# Schema_Plan_A.net
KiCad netlist of a schematic drawn in EasyEDA
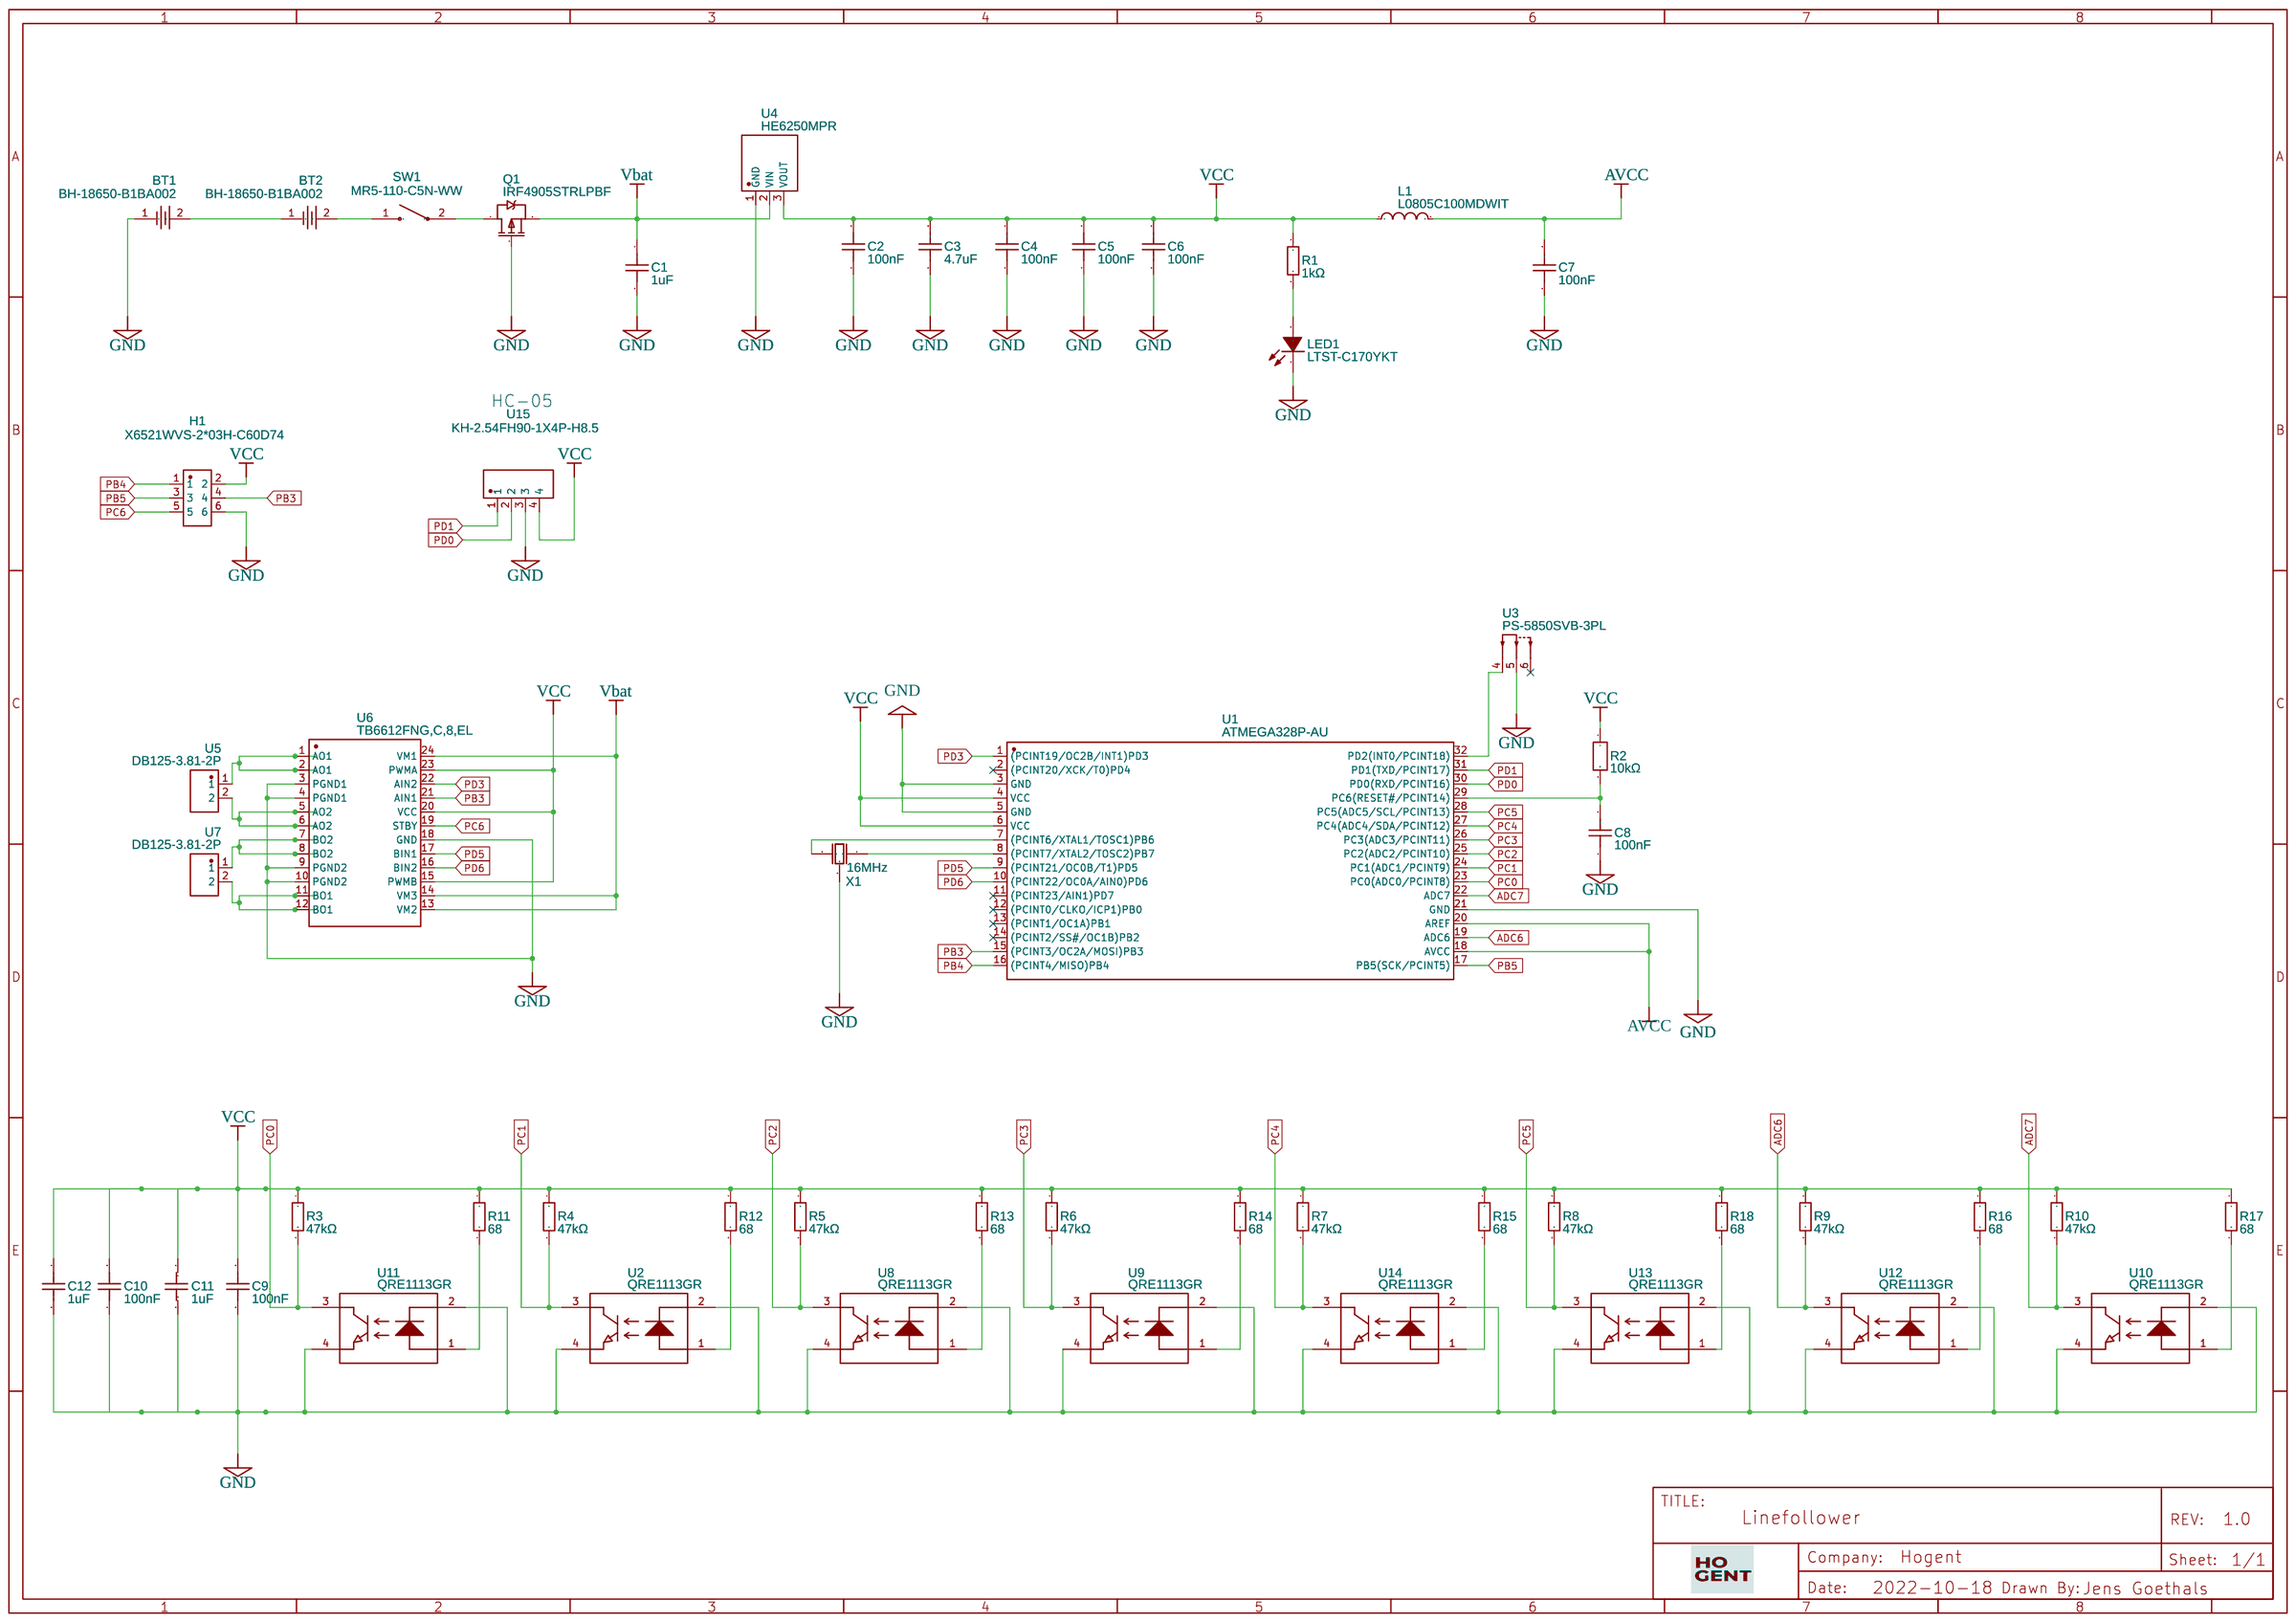
[diagram p0: schematic sheet]

(export (version "E")
  (design (tool "Eeschema 10.0.6"))
  (components
    (comp (ref "BT1")
      (value "BH-18650-B1BA002")
      (fields (field (name "BOM_Supplier Part") "C2988620"))
      (libsource (lib "") (part "BH-18650-B1BA002"))
    )
    (comp (ref "BT2")
      (value "BH-18650-B1BA002")
      (fields (field (name "BOM_Supplier Part") "C2988620"))
      (libsource (lib "") (part "BH-18650-B1BA002"))
    )
    (comp (ref "C1")
      (value "1uF")
      (fields
        (field (name "BOM_Manufacturer Part") "LMK212BJ105KD-T")
        (field (name "BOM_Supplier Part") "C92812")
      )
      (libsource (lib "") (part "LMK212BJ105KD-T_1"))
    )
    (comp (ref "C2")
      (value "100nF")
      (fields
        (field (name "BOM_Manufacturer Part") "LMK212SD104KG-T")
        (field (name "BOM_Supplier Part") "C386062")
      )
      (libsource (lib "") (part "LMK212SD104KG-T"))
    )
    (comp (ref "C3")
      (value "4.7uF")
      (fields
        (field (name "BOM_Manufacturer Part") "GCM21BC71A475KA73L")
        (field (name "BOM_Supplier Part") "C126583")
      )
      (libsource (lib "") (part "GCM21BC71A475KA73L"))
    )
    (comp (ref "C4")
      (value "100nF")
      (fields
        (field (name "BOM_Manufacturer Part") "LMK212SD104KG-T")
        (field (name "BOM_Supplier Part") "C386062")
      )
      (libsource (lib "") (part "LMK212SD104KG-T"))
    )
    (comp (ref "C5")
      (value "100nF")
      (fields
        (field (name "BOM_Manufacturer Part") "LMK212SD104KG-T")
        (field (name "BOM_Supplier Part") "C386062")
      )
      (libsource (lib "") (part "LMK212SD104KG-T"))
    )
    (comp (ref "C6")
      (value "100nF")
      (fields
        (field (name "BOM_Manufacturer Part") "LMK212SD104KG-T")
        (field (name "BOM_Supplier Part") "C386062")
      )
      (libsource (lib "") (part "LMK212SD104KG-T"))
    )
    (comp (ref "C7")
      (value "100nF")
      (fields
        (field (name "BOM_Manufacturer Part") "LMK212SD104KG-T")
        (field (name "BOM_Supplier Part") "C386062")
      )
      (libsource (lib "") (part "LMK212SD104KG-T"))
    )
    (comp (ref "C8")
      (value "100nF")
      (fields
        (field (name "BOM_Manufacturer Part") "LMK212SD104KG-T")
        (field (name "BOM_Supplier Part") "C386062")
      )
      (libsource (lib "") (part "LMK212SD104KG-T"))
    )
    (comp (ref "C9")
      (value "100nF")
      (fields
        (field (name "BOM_Manufacturer Part") "LMK212SD104KG-T")
        (field (name "BOM_Supplier Part") "C386062")
      )
      (libsource (lib "") (part "LMK212SD104KG-T"))
    )
    (comp (ref "C10")
      (value "100nF")
      (fields
        (field (name "BOM_Manufacturer Part") "LMK212SD104KG-T")
        (field (name "BOM_Supplier Part") "C386062")
      )
      (libsource (lib "") (part "LMK212SD104KG-T"))
    )
    (comp (ref "C11")
      (value "1uF")
      (fields
        (field (name "BOM_Manufacturer Part") "LMK212BJ105KD-T")
        (field (name "BOM_Supplier Part") "C92812")
      )
      (libsource (lib "") (part "LMK212BJ105KD-T"))
    )
    (comp (ref "C12")
      (value "1uF")
      (fields
        (field (name "BOM_Manufacturer Part") "LMK212BJ105KD-T")
        (field (name "BOM_Supplier Part") "C92812")
      )
      (libsource (lib "") (part "LMK212BJ105KD-T_1"))
    )
    (comp (ref "H1")
      (value "X6521WVS-2*03H-C60D74")
      (fields (field (name "BOM_Supplier Part") "C780054"))
      (libsource (lib "") (part "X6521WVS-2*03H-C60D74"))
    )
    (comp (ref "L1")
      (value "L0805C100MDWIT")
      (fields (field (name "BOM_Supplier Part") "C696787"))
      (libsource (lib "") (part "L0805C100MDWIT"))
    )
    (comp (ref "LED1")
      (value "LTST-C170YKT")
      (fields (field (name "BOM_Supplier Part") "C125092"))
      (libsource (lib "") (part "LTST-C170YKT"))
    )
    (comp (ref "Q1")
      (value "IRF4905STRLPBF")
      (fields (field (name "BOM_Supplier Part") "C2620"))
      (libsource (lib "") (part "IRF4905STRLPBF"))
    )
    (comp (ref "R1")
      (value "1kΩ")
      (fields
        (field (name "BOM_Manufacturer Part") "ARG05BTC1001")
        (field (name "BOM_Supplier Part") "C309081")
      )
      (libsource (lib "") (part "ARG05BTC1001"))
    )
    (comp (ref "R2")
      (value "10kΩ")
      (fields
        (field (name "BOM_Manufacturer Part") "ARG05BTC1002")
        (field (name "BOM_Supplier Part") "C406725")
      )
      (libsource (lib "") (part "ARG05BTC1002"))
    )
    (comp (ref "R3")
      (value "47kΩ")
      (fields
        (field (name "BOM_Manufacturer Part") "AECR0805F47K0K9")
        (field (name "BOM_Supplier Part") "C328397")
      )
      (libsource (lib "") (part "AECR0805F47K0K9"))
    )
    (comp (ref "R4")
      (value "47kΩ")
      (fields
        (field (name "BOM_Manufacturer Part") "AECR0805F47K0K9")
        (field (name "BOM_Supplier Part") "C328397")
      )
      (libsource (lib "") (part "AECR0805F47K0K9"))
    )
    (comp (ref "R5")
      (value "47kΩ")
      (fields
        (field (name "BOM_Manufacturer Part") "AECR0805F47K0K9")
        (field (name "BOM_Supplier Part") "C328397")
      )
      (libsource (lib "") (part "AECR0805F47K0K9"))
    )
    (comp (ref "R6")
      (value "47kΩ")
      (fields
        (field (name "BOM_Manufacturer Part") "AECR0805F47K0K9")
        (field (name "BOM_Supplier Part") "C328397")
      )
      (libsource (lib "") (part "AECR0805F47K0K9"))
    )
    (comp (ref "R7")
      (value "47kΩ")
      (fields
        (field (name "BOM_Manufacturer Part") "AECR0805F47K0K9")
        (field (name "BOM_Supplier Part") "C328397")
      )
      (libsource (lib "") (part "AECR0805F47K0K9"))
    )
    (comp (ref "R8")
      (value "47kΩ")
      (fields
        (field (name "BOM_Manufacturer Part") "AECR0805F47K0K9")
        (field (name "BOM_Supplier Part") "C328397")
      )
      (libsource (lib "") (part "AECR0805F47K0K9"))
    )
    (comp (ref "R9")
      (value "47kΩ")
      (fields
        (field (name "BOM_Manufacturer Part") "AECR0805F47K0K9")
        (field (name "BOM_Supplier Part") "C328397")
      )
      (libsource (lib "") (part "AECR0805F47K0K9"))
    )
    (comp (ref "R10")
      (value "47kΩ")
      (fields
        (field (name "BOM_Manufacturer Part") "AECR0805F47K0K9")
        (field (name "BOM_Supplier Part") "C328397")
      )
      (libsource (lib "") (part "AECR0805F47K0K9"))
    )
    (comp (ref "R11")
      (value "68")
      (fields
        (field (name "BOM_Manufacturer Part") "RC0805FR-0768RL")
        (field (name "BOM_Supplier Part") "C137498")
      )
      (libsource (lib "") (part "RC0805FR-0768RL"))
    )
    (comp (ref "R12")
      (value "68")
      (fields
        (field (name "BOM_Manufacturer Part") "RC0805FR-0768RL")
        (field (name "BOM_Supplier Part") "C137498")
      )
      (libsource (lib "") (part "RC0805FR-0768RL"))
    )
    (comp (ref "R13")
      (value "68")
      (fields
        (field (name "BOM_Manufacturer Part") "RC0805FR-0768RL")
        (field (name "BOM_Supplier Part") "C137498")
      )
      (libsource (lib "") (part "RC0805FR-0768RL"))
    )
    (comp (ref "R14")
      (value "68")
      (fields
        (field (name "BOM_Manufacturer Part") "RC0805FR-0768RL")
        (field (name "BOM_Supplier Part") "C137498")
      )
      (libsource (lib "") (part "RC0805FR-0768RL"))
    )
    (comp (ref "R15")
      (value "68")
      (fields
        (field (name "BOM_Manufacturer Part") "RC0805FR-0768RL")
        (field (name "BOM_Supplier Part") "C137498")
      )
      (libsource (lib "") (part "RC0805FR-0768RL"))
    )
    (comp (ref "R16")
      (value "68")
      (fields
        (field (name "BOM_Manufacturer Part") "RC0805FR-0768RL")
        (field (name "BOM_Supplier Part") "C137498")
      )
      (libsource (lib "") (part "RC0805FR-0768RL"))
    )
    (comp (ref "R17")
      (value "68")
      (fields
        (field (name "BOM_Manufacturer Part") "RC0805FR-0768RL")
        (field (name "BOM_Supplier Part") "C137498")
      )
      (libsource (lib "") (part "RC0805FR-0768RL"))
    )
    (comp (ref "R18")
      (value "68")
      (fields
        (field (name "BOM_Manufacturer Part") "RC0805FR-0768RL")
        (field (name "BOM_Supplier Part") "C137498")
      )
      (libsource (lib "") (part "RC0805FR-0768RL"))
    )
    (comp (ref "SW1")
      (value "MR5-110-C5N-WW")
      (fields (field (name "BOM_Supplier Part") "C2829507"))
      (libsource (lib "") (part "MR5-110-C5N-WW"))
    )
    (comp (ref "U1")
      (value "ATMEGA328P-AU")
      (fields (field (name "BOM_Supplier Part") "C14877"))
      (libsource (lib "") (part "ATMEGA328P-AU"))
    )
    (comp (ref "U2")
      (value "QRE1113GR")
      (fields (field (name "BOM_Supplier Part") "C232862"))
      (libsource (lib "") (part "QRE1113GR_3"))
    )
    (comp (ref "U3")
      (value "PS-5850SVB-3PL")
      (fields (field (name "BOM_Supplier Part") "C5159077"))
      (libsource (lib "") (part "PS-5850SVB-3PL"))
    )
    (comp (ref "U4")
      (value "HE6250MPR")
      (fields (field (name "BOM_Supplier Part") "C711940"))
      (libsource (lib "") (part "HE6250MPR"))
    )
    (comp (ref "U5")
      (value "DB125-3.81-2P")
      (fields (field (name "BOM_Supplier Part") "C395878"))
      (libsource (lib "") (part "DB125-3.81-2P"))
    )
    (comp (ref "U6")
      (value "TB6612FNG,C,8,EL")
      (fields (field (name "BOM_Supplier Part") "C141517"))
      (libsource (lib "") (part "Unknown_500_-570"))
    )
    (comp (ref "U7")
      (value "DB125-3.81-2P")
      (fields (field (name "BOM_Supplier Part") "C395878"))
      (libsource (lib "") (part "DB125-3.81-2P"))
    )
    (comp (ref "U8")
      (value "QRE1113GR")
      (fields (field (name "BOM_Supplier Part") "C232862"))
      (libsource (lib "") (part "QRE1113GR"))
    )
    (comp (ref "U9")
      (value "QRE1113GR")
      (fields (field (name "BOM_Supplier Part") "C232862"))
      (libsource (lib "") (part "QRE1113GR_4"))
    )
    (comp (ref "U10")
      (value "QRE1113GR")
      (fields (field (name "BOM_Supplier Part") "C232862"))
      (libsource (lib "") (part "QRE1113GR_2"))
    )
    (comp (ref "U11")
      (value "QRE1113GR")
      (fields (field (name "BOM_Supplier Part") "C232862"))
      (libsource (lib "") (part "QRE1113GR_2"))
    )
    (comp (ref "U12")
      (value "QRE1113GR")
      (fields (field (name "BOM_Supplier Part") "C232862"))
      (libsource (lib "") (part "QRE1113GR_6"))
    )
    (comp (ref "U13")
      (value "QRE1113GR")
      (fields (field (name "BOM_Supplier Part") "C232862"))
      (libsource (lib "") (part "QRE1113GR_1"))
    )
    (comp (ref "U14")
      (value "QRE1113GR")
      (fields (field (name "BOM_Supplier Part") "C232862"))
      (libsource (lib "") (part "QRE1113GR_5"))
    )
    (comp (ref "U15")
      (value "KH-2.54FH90-1X4P-H8.5")
      (fields (field (name "BOM_Supplier Part") "C2932680"))
      (libsource (lib "") (part "KH-2.54FH90-1X4P-H8.5"))
    )
    (comp (ref "X1")
      (value "16MHz")
      (fields
        (field (name "BOM_Manufacturer Part") "CSTNE16M0V53C000R0")
        (field (name "BOM_Supplier Part") "C882606")
      )
      (libsource (lib "") (part "CSTNE16M0V53C000R0"))
    )
  )
  (nets
    (net (code "1") (name "ADC6") (class "Default")
      (node (ref "R9") (pin "2") (pinfunction "2_2") (pintype "unspecified"))
      (node (ref "U1") (pin "19") (pinfunction "ADC6_19") (pintype "unspecified"))
      (node (ref "U12") (pin "3") (pinfunction "3_3") (pintype "input"))
    )
    (net (code "2") (name "ADC7") (class "Default")
      (node (ref "R10") (pin "2") (pinfunction "2_2") (pintype "unspecified"))
      (node (ref "U1") (pin "22") (pinfunction "ADC7_22") (pintype "unspecified"))
      (node (ref "U10") (pin "3") (pinfunction "3_3") (pintype "input"))
    )
    (net (code "3") (name "AVCC") (class "Default")
      (node (ref "C7") (pin "2") (pinfunction "2_2") (pintype "unspecified"))
      (node (ref "L1") (pin "2") (pinfunction "2_2") (pintype "unspecified"))
      (node (ref "U1") (pin "18") (pinfunction "AVCC_18") (pintype "unspecified"))
      (node (ref "U1") (pin "20") (pinfunction "AREF_20") (pintype "unspecified"))
    )
    (net (code "4") (name "GND") (class "Default")
      (node (ref "BT1") (pin "1") (pinfunction "1_1") (pintype "input"))
      (node (ref "C1") (pin "2") (pinfunction "2_2") (pintype "unspecified"))
      (node (ref "C10") (pin "1") (pinfunction "1_1") (pintype "unspecified"))
      (node (ref "C11") (pin "2") (pinfunction "2_2") (pintype "unspecified"))
      (node (ref "C12") (pin "2") (pinfunction "2_2") (pintype "unspecified"))
      (node (ref "C2") (pin "1") (pinfunction "1_1") (pintype "unspecified"))
      (node (ref "C3") (pin "1") (pinfunction "1_1") (pintype "unspecified"))
      (node (ref "C4") (pin "1") (pinfunction "1_1") (pintype "unspecified"))
      (node (ref "C5") (pin "1") (pinfunction "1_1") (pintype "unspecified"))
      (node (ref "C6") (pin "1") (pinfunction "1_1") (pintype "unspecified"))
      (node (ref "C7") (pin "1") (pinfunction "1_1") (pintype "unspecified"))
      (node (ref "C8") (pin "1") (pinfunction "1_1") (pintype "unspecified"))
      (node (ref "C9") (pin "1") (pinfunction "1_1") (pintype "unspecified"))
      (node (ref "H1") (pin "6") (pinfunction "6_6") (pintype "unspecified"))
      (node (ref "LED1") (pin "1") (pinfunction "1_1") (pintype "unspecified"))
      (node (ref "Q1") (pin "1") (pinfunction "G_1") (pintype "unspecified"))
      (node (ref "U1") (pin "21") (pinfunction "GND_21") (pintype "unspecified"))
      (node (ref "U1") (pin "3") (pinfunction "GND_3") (pintype "unspecified"))
      (node (ref "U1") (pin "5") (pinfunction "GND_5") (pintype "unspecified"))
      (node (ref "U10") (pin "2") (pinfunction "2_2") (pintype "input"))
      (node (ref "U10") (pin "4") (pinfunction "4_4") (pintype "input"))
      (node (ref "U11") (pin "2") (pinfunction "2_2") (pintype "input"))
      (node (ref "U11") (pin "4") (pinfunction "4_4") (pintype "input"))
      (node (ref "U12") (pin "2") (pinfunction "2_2") (pintype "input"))
      (node (ref "U12") (pin "4") (pinfunction "4_4") (pintype "input"))
      (node (ref "U13") (pin "2") (pinfunction "2_2") (pintype "input"))
      (node (ref "U13") (pin "4") (pinfunction "4_4") (pintype "input"))
      (node (ref "U14") (pin "2") (pinfunction "2_2") (pintype "input"))
      (node (ref "U14") (pin "4") (pinfunction "4_4") (pintype "input"))
      (node (ref "U15") (pin "3") (pinfunction "3_3") (pintype "unspecified"))
      (node (ref "U2") (pin "2") (pinfunction "2_2") (pintype "input"))
      (node (ref "U2") (pin "4") (pinfunction "4_4") (pintype "input"))
      (node (ref "U3") (pin "5") (pinfunction "5_5") (pintype "unspecified"))
      (node (ref "U4") (pin "1") (pinfunction "GND_1") (pintype "unspecified"))
      (node (ref "U6") (pin "10") (pinfunction "PGND2_10") (pintype "unspecified"))
      (node (ref "U6") (pin "18") (pinfunction "GND_18") (pintype "unspecified"))
      (node (ref "U6") (pin "3") (pinfunction "PGND1_3") (pintype "unspecified"))
      (node (ref "U6") (pin "4") (pinfunction "PGND1_4") (pintype "unspecified"))
      (node (ref "U6") (pin "9") (pinfunction "PGND2_9") (pintype "unspecified"))
      (node (ref "U8") (pin "2") (pinfunction "2_2") (pintype "input"))
      (node (ref "U8") (pin "4") (pinfunction "4_4") (pintype "input"))
      (node (ref "U9") (pin "2") (pinfunction "2_2") (pintype "input"))
      (node (ref "U9") (pin "4") (pinfunction "4_4") (pintype "input"))
      (node (ref "X1") (pin "2") (pinfunction "GND_2") (pintype "input"))
    )
    (net (code "5") (name "Net-(BT1-Pad2)") (class "Default")
      (node (ref "BT1") (pin "2") (pinfunction "2_2") (pintype "input"))
      (node (ref "BT2") (pin "1") (pinfunction "1_1") (pintype "input"))
    )
    (net (code "6") (name "Net-(BT2-Pad2)") (class "Default")
      (node (ref "BT2") (pin "2") (pinfunction "2_2") (pintype "input"))
      (node (ref "SW1") (pin "1") (pinfunction "1_1") (pintype "unspecified"))
    )
    (net (code "7") (name "Net-(LED1-Pad2)") (class "Default")
      (node (ref "LED1") (pin "2") (pinfunction "2_2") (pintype "unspecified"))
      (node (ref "R1") (pin "2") (pinfunction "2_2") (pintype "unspecified"))
    )
    (net (code "8") (name "Net-(Q1-D)") (class "Default")
      (node (ref "Q1") (pin "4") (pinfunction "D_4") (pintype "unspecified"))
      (node (ref "SW1") (pin "2") (pinfunction "2_2") (pintype "unspecified"))
    )
    (net (code "9") (name "Net-(R11-Pad2)") (class "Default")
      (node (ref "R11") (pin "2") (pinfunction "2_2") (pintype "input"))
      (node (ref "U11") (pin "1") (pinfunction "1_1") (pintype "input"))
    )
    (net (code "10") (name "Net-(R12-Pad2)") (class "Default")
      (node (ref "R12") (pin "2") (pinfunction "2_2") (pintype "input"))
      (node (ref "U2") (pin "1") (pinfunction "1_1") (pintype "input"))
    )
    (net (code "11") (name "Net-(R13-Pad2)") (class "Default")
      (node (ref "R13") (pin "2") (pinfunction "2_2") (pintype "input"))
      (node (ref "U8") (pin "1") (pinfunction "1_1") (pintype "input"))
    )
    (net (code "12") (name "Net-(R14-Pad2)") (class "Default")
      (node (ref "R14") (pin "2") (pinfunction "2_2") (pintype "input"))
      (node (ref "U9") (pin "1") (pinfunction "1_1") (pintype "input"))
    )
    (net (code "13") (name "Net-(R15-Pad2)") (class "Default")
      (node (ref "R15") (pin "2") (pinfunction "2_2") (pintype "input"))
      (node (ref "U14") (pin "1") (pinfunction "1_1") (pintype "input"))
    )
    (net (code "14") (name "Net-(R16-Pad2)") (class "Default")
      (node (ref "R16") (pin "2") (pinfunction "2_2") (pintype "input"))
      (node (ref "U12") (pin "1") (pinfunction "1_1") (pintype "input"))
    )
    (net (code "15") (name "Net-(R17-Pad2)") (class "Default")
      (node (ref "R17") (pin "2") (pinfunction "2_2") (pintype "input"))
      (node (ref "U10") (pin "1") (pinfunction "1_1") (pintype "input"))
    )
    (net (code "16") (name "Net-(R18-Pad2)") (class "Default")
      (node (ref "R18") (pin "2") (pinfunction "2_2") (pintype "input"))
      (node (ref "U13") (pin "1") (pinfunction "1_1") (pintype "input"))
    )
    (net (code "17") (name "Net-(U1-(PCINT6{slash}XTAL1{slash}TOSC1)PB6)") (class "Default")
      (node (ref "U1") (pin "7") (pinfunction "(PCINT6/XTAL1/TOSC1)PB6_7") (pintype "unspecified"))
      (node (ref "X1") (pin "3") (pinfunction "OSC2_3") (pintype "input"))
    )
    (net (code "18") (name "Net-(U1-(PCINT7{slash}XTAL2{slash}TOSC2)PB7)") (class "Default")
      (node (ref "U1") (pin "8") (pinfunction "(PCINT7/XTAL2/TOSC2)PB7_8") (pintype "unspecified"))
      (node (ref "X1") (pin "1") (pinfunction "OSC1_1") (pintype "input"))
    )
    (net (code "19") (name "Net-(U1-PC6(RESET#{slash}PCINT14))") (class "Default")
      (node (ref "C8") (pin "2") (pinfunction "2_2") (pintype "unspecified"))
      (node (ref "R2") (pin "2") (pinfunction "2_2") (pintype "unspecified"))
      (node (ref "U1") (pin "29") (pinfunction "PC6(RESET#/PCINT14)_29") (pintype "unspecified"))
    )
    (net (code "20") (name "Net-(U1-PD2(INT0{slash}PCINT18))") (class "Default")
      (node (ref "U1") (pin "32") (pinfunction "PD2(INT0/PCINT18)_32") (pintype "unspecified"))
      (node (ref "U3") (pin "4") (pinfunction "4_4") (pintype "unspecified"))
    )
    (net (code "21") (name "Net-(U5-Pad1)") (class "Default")
      (node (ref "U5") (pin "1") (pinfunction "1_1") (pintype "unspecified"))
      (node (ref "U6") (pin "1") (pinfunction "AO1_1") (pintype "unspecified"))
      (node (ref "U6") (pin "2") (pinfunction "AO1_2") (pintype "unspecified"))
    )
    (net (code "22") (name "Net-(U5-Pad2)") (class "Default")
      (node (ref "U5") (pin "2") (pinfunction "2_2") (pintype "unspecified"))
      (node (ref "U6") (pin "5") (pinfunction "AO2_5") (pintype "unspecified"))
      (node (ref "U6") (pin "6") (pinfunction "AO2_6") (pintype "unspecified"))
    )
    (net (code "23") (name "Net-(U6-BO1-Pad11)") (class "Default")
      (node (ref "U6") (pin "11") (pinfunction "BO1_11") (pintype "unspecified"))
      (node (ref "U6") (pin "12") (pinfunction "BO1_12") (pintype "unspecified"))
      (node (ref "U7") (pin "2") (pinfunction "2_2") (pintype "unspecified"))
    )
    (net (code "24") (name "Net-(U6-BO2-Pad7)") (class "Default")
      (node (ref "U6") (pin "7") (pinfunction "BO2_7") (pintype "unspecified"))
      (node (ref "U6") (pin "8") (pinfunction "BO2_8") (pintype "unspecified"))
      (node (ref "U7") (pin "1") (pinfunction "1_1") (pintype "unspecified"))
    )
    (net (code "25") (name "PB3") (class "Default")
      (node (ref "H1") (pin "4") (pinfunction "4_4") (pintype "unspecified"))
      (node (ref "U1") (pin "15") (pinfunction "(PCINT3/OC2A/MOSI)PB3_15") (pintype "unspecified"))
      (node (ref "U6") (pin "21") (pinfunction "AIN1_21") (pintype "unspecified"))
    )
    (net (code "26") (name "PB4") (class "Default")
      (node (ref "H1") (pin "1") (pinfunction "1_1") (pintype "unspecified"))
      (node (ref "U1") (pin "16") (pinfunction "(PCINT4/MISO)PB4_16") (pintype "unspecified"))
    )
    (net (code "27") (name "PB5") (class "Default")
      (node (ref "H1") (pin "3") (pinfunction "3_3") (pintype "unspecified"))
      (node (ref "U1") (pin "17") (pinfunction "PB5(SCK/PCINT5)_17") (pintype "unspecified"))
    )
    (net (code "28") (name "PC0") (class "Default")
      (node (ref "R3") (pin "2") (pinfunction "2_2") (pintype "unspecified"))
      (node (ref "U1") (pin "23") (pinfunction "PC0(ADC0/PCINT8)_23") (pintype "unspecified"))
      (node (ref "U11") (pin "3") (pinfunction "3_3") (pintype "input"))
    )
    (net (code "29") (name "PC1") (class "Default")
      (node (ref "R4") (pin "2") (pinfunction "2_2") (pintype "unspecified"))
      (node (ref "U1") (pin "24") (pinfunction "PC1(ADC1/PCINT9)_24") (pintype "unspecified"))
      (node (ref "U2") (pin "3") (pinfunction "3_3") (pintype "input"))
    )
    (net (code "30") (name "PC2") (class "Default")
      (node (ref "R5") (pin "2") (pinfunction "2_2") (pintype "unspecified"))
      (node (ref "U1") (pin "25") (pinfunction "PC2(ADC2/PCINT10)_25") (pintype "unspecified"))
      (node (ref "U8") (pin "3") (pinfunction "3_3") (pintype "input"))
    )
    (net (code "31") (name "PC3") (class "Default")
      (node (ref "R6") (pin "2") (pinfunction "2_2") (pintype "unspecified"))
      (node (ref "U1") (pin "26") (pinfunction "PC3(ADC3/PCINT11)_26") (pintype "unspecified"))
      (node (ref "U9") (pin "3") (pinfunction "3_3") (pintype "input"))
    )
    (net (code "32") (name "PC4") (class "Default")
      (node (ref "R7") (pin "2") (pinfunction "2_2") (pintype "unspecified"))
      (node (ref "U1") (pin "27") (pinfunction "PC4(ADC4/SDA/PCINT12)_27") (pintype "unspecified"))
      (node (ref "U14") (pin "3") (pinfunction "3_3") (pintype "input"))
    )
    (net (code "33") (name "PC5") (class "Default")
      (node (ref "R8") (pin "2") (pinfunction "2_2") (pintype "unspecified"))
      (node (ref "U1") (pin "28") (pinfunction "PC5(ADC5/SCL/PCINT13)_28") (pintype "unspecified"))
      (node (ref "U13") (pin "3") (pinfunction "3_3") (pintype "input"))
    )
    (net (code "34") (name "PC6") (class "Default")
      (node (ref "H1") (pin "5") (pinfunction "5_5") (pintype "unspecified"))
      (node (ref "U6") (pin "19") (pinfunction "STBY_19") (pintype "unspecified"))
    )
    (net (code "35") (name "PD0") (class "Default")
      (node (ref "U1") (pin "30") (pinfunction "PD0(RXD/PCINT16)_30") (pintype "unspecified"))
      (node (ref "U15") (pin "2") (pinfunction "2_2") (pintype "unspecified"))
    )
    (net (code "36") (name "PD1") (class "Default")
      (node (ref "U1") (pin "31") (pinfunction "PD1(TXD/PCINT17)_31") (pintype "unspecified"))
      (node (ref "U15") (pin "1") (pinfunction "1_1") (pintype "unspecified"))
    )
    (net (code "37") (name "PD3") (class "Default")
      (node (ref "U1") (pin "1") (pinfunction "(PCINT19/OC2B/INT1)PD3_1") (pintype "unspecified"))
      (node (ref "U6") (pin "22") (pinfunction "AIN2_22") (pintype "unspecified"))
    )
    (net (code "38") (name "PD5") (class "Default")
      (node (ref "U1") (pin "9") (pinfunction "(PCINT21/OC0B/T1)PD5_9") (pintype "unspecified"))
      (node (ref "U6") (pin "17") (pinfunction "BIN1_17") (pintype "unspecified"))
    )
    (net (code "39") (name "PD6") (class "Default")
      (node (ref "U1") (pin "10") (pinfunction "(PCINT22/OC0A/AIN0)PD6_10") (pintype "unspecified"))
      (node (ref "U6") (pin "16") (pinfunction "BIN2_16") (pintype "unspecified"))
    )
    (net (code "40") (name "VCC") (class "Default")
      (node (ref "C10") (pin "2") (pinfunction "2_2") (pintype "unspecified"))
      (node (ref "C11") (pin "1") (pinfunction "1_1") (pintype "unspecified"))
      (node (ref "C12") (pin "1") (pinfunction "1_1") (pintype "unspecified"))
      (node (ref "C2") (pin "2") (pinfunction "2_2") (pintype "unspecified"))
      (node (ref "C3") (pin "2") (pinfunction "2_2") (pintype "unspecified"))
      (node (ref "C4") (pin "2") (pinfunction "2_2") (pintype "unspecified"))
      (node (ref "C5") (pin "2") (pinfunction "2_2") (pintype "unspecified"))
      (node (ref "C6") (pin "2") (pinfunction "2_2") (pintype "unspecified"))
      (node (ref "C9") (pin "2") (pinfunction "2_2") (pintype "unspecified"))
      (node (ref "H1") (pin "2") (pinfunction "2_2") (pintype "unspecified"))
      (node (ref "L1") (pin "1") (pinfunction "1_1") (pintype "unspecified"))
      (node (ref "R1") (pin "1") (pinfunction "1_1") (pintype "unspecified"))
      (node (ref "R10") (pin "1") (pinfunction "1_1") (pintype "unspecified"))
      (node (ref "R11") (pin "1") (pinfunction "1_1") (pintype "input"))
      (node (ref "R12") (pin "1") (pinfunction "1_1") (pintype "input"))
      (node (ref "R13") (pin "1") (pinfunction "1_1") (pintype "input"))
      (node (ref "R14") (pin "1") (pinfunction "1_1") (pintype "input"))
      (node (ref "R15") (pin "1") (pinfunction "1_1") (pintype "input"))
      (node (ref "R16") (pin "1") (pinfunction "1_1") (pintype "input"))
      (node (ref "R17") (pin "1") (pinfunction "1_1") (pintype "input"))
      (node (ref "R18") (pin "1") (pinfunction "1_1") (pintype "input"))
      (node (ref "R2") (pin "1") (pinfunction "1_1") (pintype "unspecified"))
      (node (ref "R3") (pin "1") (pinfunction "1_1") (pintype "unspecified"))
      (node (ref "R4") (pin "1") (pinfunction "1_1") (pintype "unspecified"))
      (node (ref "R5") (pin "1") (pinfunction "1_1") (pintype "unspecified"))
      (node (ref "R6") (pin "1") (pinfunction "1_1") (pintype "unspecified"))
      (node (ref "R7") (pin "1") (pinfunction "1_1") (pintype "unspecified"))
      (node (ref "R8") (pin "1") (pinfunction "1_1") (pintype "unspecified"))
      (node (ref "R9") (pin "1") (pinfunction "1_1") (pintype "unspecified"))
      (node (ref "U1") (pin "4") (pinfunction "VCC_4") (pintype "unspecified"))
      (node (ref "U1") (pin "6") (pinfunction "VCC_6") (pintype "unspecified"))
      (node (ref "U15") (pin "4") (pinfunction "4_4") (pintype "unspecified"))
      (node (ref "U4") (pin "3") (pinfunction "VOUT_3") (pintype "unspecified"))
      (node (ref "U6") (pin "15") (pinfunction "PWMB_15") (pintype "unspecified"))
      (node (ref "U6") (pin "20") (pinfunction "VCC_20") (pintype "unspecified"))
      (node (ref "U6") (pin "23") (pinfunction "PWMA_23") (pintype "unspecified"))
    )
    (net (code "41") (name "Vbat") (class "Default")
      (node (ref "C1") (pin "1") (pinfunction "1_1") (pintype "unspecified"))
      (node (ref "Q1") (pin "3") (pinfunction "S_3") (pintype "unspecified"))
      (node (ref "U4") (pin "2") (pinfunction "VIN_2") (pintype "unspecified"))
      (node (ref "U6") (pin "13") (pinfunction "VM2_13") (pintype "unspecified"))
      (node (ref "U6") (pin "14") (pinfunction "VM3_14") (pintype "unspecified"))
      (node (ref "U6") (pin "24") (pinfunction "VM1_24") (pintype "unspecified"))
    )
    (net (code "42") (name "unconnected-(U1-(PCINT0{slash}CLKO{slash}ICP1)PB0-Pad12)") (class "Default")
      (node (ref "U1") (pin "12") (pinfunction "(PCINT0/CLKO/ICP1)PB0_12") (pintype "unspecified+no_connect"))
    )
    (net (code "43") (name "unconnected-(U1-(PCINT1{slash}OC1A)PB1-Pad13)") (class "Default")
      (node (ref "U1") (pin "13") (pinfunction "(PCINT1/OC1A)PB1_13") (pintype "unspecified+no_connect"))
    )
    (net (code "44") (name "unconnected-(U1-(PCINT2{slash}SS#{slash}OC1B)PB2-Pad14)") (class "Default")
      (node (ref "U1") (pin "14") (pinfunction "(PCINT2/SS#/OC1B)PB2_14") (pintype "unspecified+no_connect"))
    )
    (net (code "45") (name "unconnected-(U1-(PCINT20{slash}XCK{slash}T0)PD4-Pad2)") (class "Default")
      (node (ref "U1") (pin "2") (pinfunction "(PCINT20/XCK/T0)PD4_2") (pintype "unspecified+no_connect"))
    )
    (net (code "46") (name "unconnected-(U1-(PCINT23{slash}AIN1)PD7-Pad11)") (class "Default")
      (node (ref "U1") (pin "11") (pinfunction "(PCINT23/AIN1)PD7_11") (pintype "unspecified+no_connect"))
    )
    (net (code "47") (name "unconnected-(U3-Pad6)") (class "Default")
      (node (ref "U3") (pin "6") (pinfunction "6_6") (pintype "unspecified+no_connect"))
    )
  )
)
